# schematic.net
KiCad netlist of a schematic drawn in EasyEDA
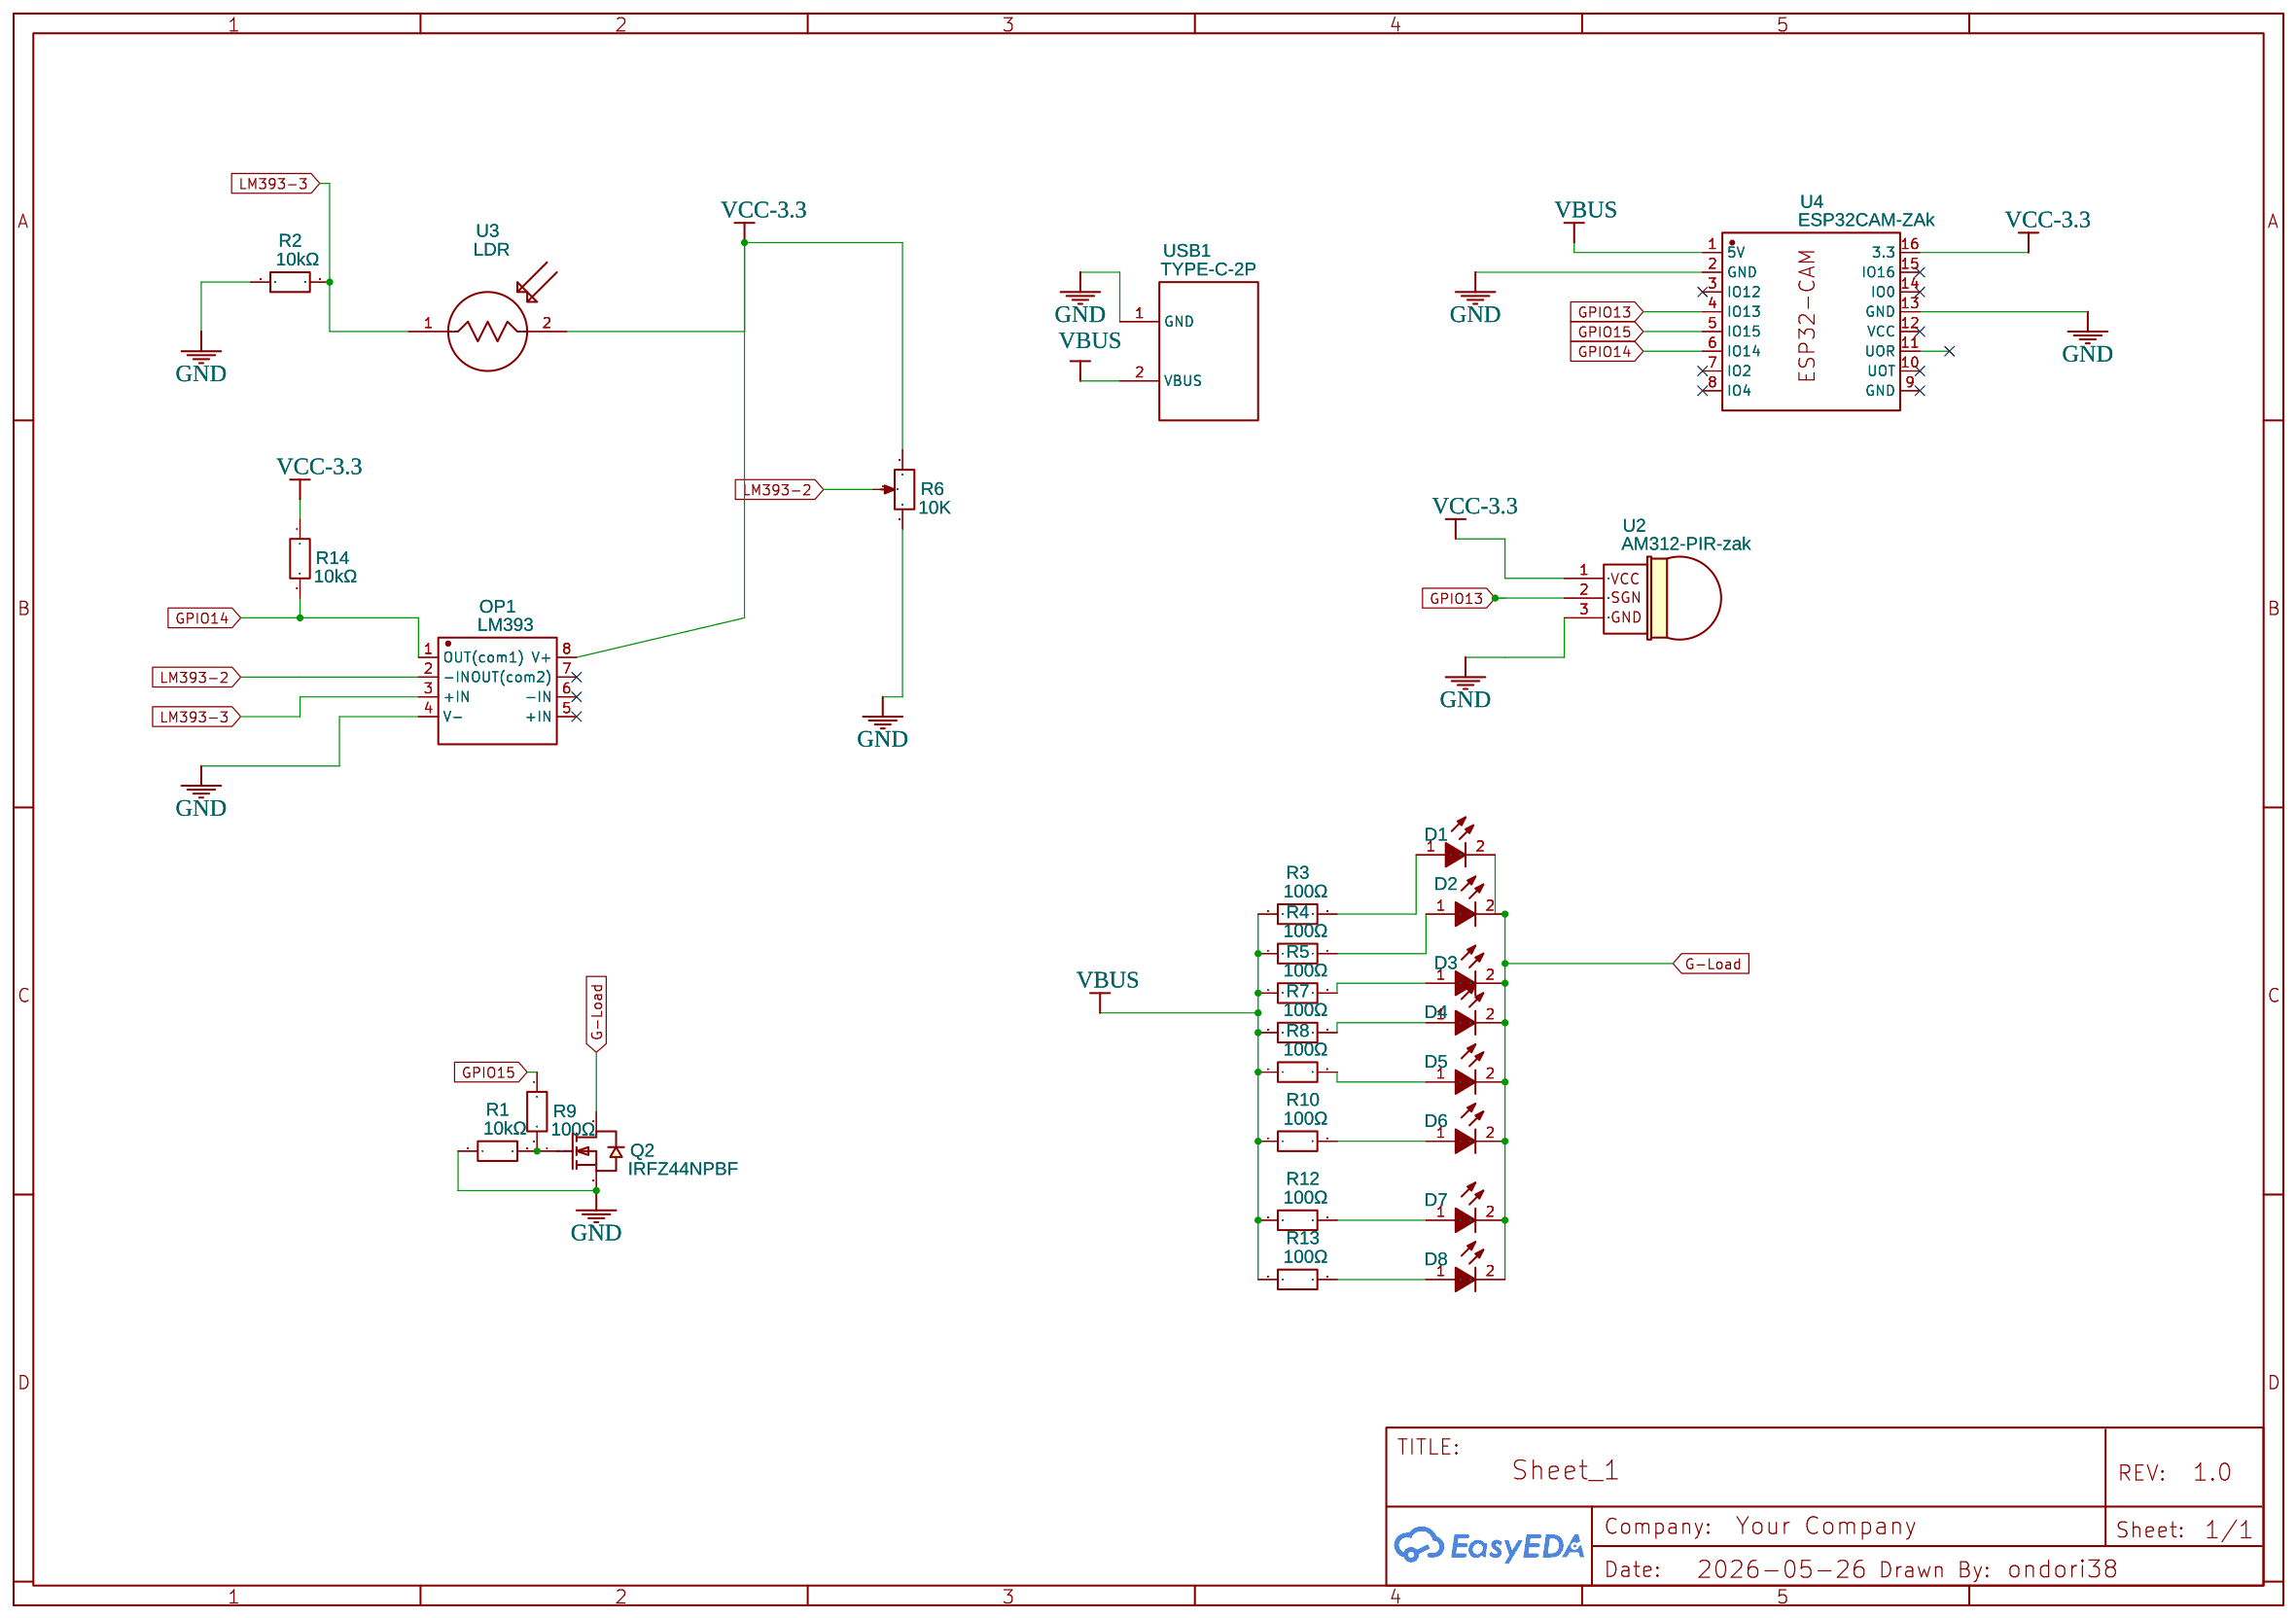
[diagram p0: schematic sheet]

(export (version "E")
  (design (tool "Eeschema 10.0.6"))
  (components
    (comp (ref "D1")
      (value "LED 2MM")
      (fields (field (name "Manufacturer Part") "5600") (field (name "Manufacturer") "VccLite"))
      (libsource (lib "") (part "LED 2MM"))
    )
    (comp (ref "D2")
      (value "LED 2MM")
      (fields (field (name "Manufacturer Part") "5600") (field (name "Manufacturer") "VccLite"))
      (libsource (lib "") (part "LED 2MM"))
    )
    (comp (ref "D3")
      (value "LED 2MM")
      (fields (field (name "Manufacturer Part") "5600") (field (name "Manufacturer") "VccLite"))
      (libsource (lib "") (part "LED 2MM"))
    )
    (comp (ref "D4")
      (value "LED 2MM")
      (fields (field (name "Manufacturer Part") "5600") (field (name "Manufacturer") "VccLite"))
      (libsource (lib "") (part "LED 2MM"))
    )
    (comp (ref "D5")
      (value "LED 2MM")
      (fields (field (name "Manufacturer Part") "5600") (field (name "Manufacturer") "VccLite"))
      (libsource (lib "") (part "LED 2MM"))
    )
    (comp (ref "D6")
      (value "LED 2MM")
      (fields (field (name "Manufacturer Part") "5600") (field (name "Manufacturer") "VccLite"))
      (libsource (lib "") (part "LED 2MM"))
    )
    (comp (ref "D7")
      (value "LED 2MM")
      (fields (field (name "Manufacturer Part") "5600") (field (name "Manufacturer") "VccLite"))
      (libsource (lib "") (part "LED 2MM"))
    )
    (comp (ref "D8")
      (value "LED 2MM")
      (fields (field (name "Manufacturer Part") "5600") (field (name "Manufacturer") "VccLite"))
      (libsource (lib "") (part "LED 2MM"))
    )
    (comp (ref "OP1") (value "LM393") (libsource (lib "") (part "LM393")))
    (comp (ref "Q2")
      (value "IRFZ44NPBF")
      (fields (field (name "Manufacturer") "Infineon(英飞凌)"))
      (libsource (lib "") (part "IRFZ44NPBF"))
    )
    (comp (ref "R1")
      (value "10kΩ")
      (fields (field (name "Manufacturer Part") "SCR1206F68K") (field (name "Manufacturer") "VO(翔胜)"))
      (libsource (lib "") (part "SCR1206F68K"))
    )
    (comp (ref "R2")
      (value "10kΩ")
      (fields (field (name "Manufacturer Part") "SCR1206F68K") (field (name "Manufacturer") "VO(翔胜)"))
      (libsource (lib "") (part "SCR1206F68K"))
    )
    (comp (ref "R3")
      (value "100Ω")
      (fields (field (name "Manufacturer Part") "SCR1206F68K") (field (name "Manufacturer") "VO(翔胜)"))
      (libsource (lib "") (part "SCR1206F68K"))
    )
    (comp (ref "R4")
      (value "100Ω")
      (fields (field (name "Manufacturer Part") "SCR1206F68K") (field (name "Manufacturer") "VO(翔胜)"))
      (libsource (lib "") (part "SCR1206F68K"))
    )
    (comp (ref "R5")
      (value "100Ω")
      (fields (field (name "Manufacturer Part") "SCR1206F68K") (field (name "Manufacturer") "VO(翔胜)"))
      (libsource (lib "") (part "SCR1206F68K"))
    )
    (comp (ref "R6")
      (value "10K")
      (fields
        (field (name "Manufacturer Part") "3296W-1-103")
        (field (name "Manufacturer") "Chengdu Guosheng Tech")
      )
      (libsource (lib "") (part "3296W-1-103_C330432"))
    )
    (comp (ref "R7")
      (value "100Ω")
      (fields (field (name "Manufacturer Part") "SCR1206F68K") (field (name "Manufacturer") "VO(翔胜)"))
      (libsource (lib "") (part "SCR1206F68K"))
    )
    (comp (ref "R8")
      (value "100Ω")
      (fields (field (name "Manufacturer Part") "SCR1206F68K") (field (name "Manufacturer") "VO(翔胜)"))
      (libsource (lib "") (part "SCR1206F68K"))
    )
    (comp (ref "R9")
      (value "100Ω")
      (fields (field (name "Manufacturer Part") "SCR1206F68K") (field (name "Manufacturer") "VO(翔胜)"))
      (libsource (lib "") (part "SCR1206F68K_1"))
    )
    (comp (ref "R10")
      (value "100Ω")
      (fields (field (name "Manufacturer Part") "SCR1206F68K") (field (name "Manufacturer") "VO(翔胜)"))
      (libsource (lib "") (part "SCR1206F68K"))
    )
    (comp (ref "R12")
      (value "100Ω")
      (fields (field (name "Manufacturer Part") "SCR1206F68K") (field (name "Manufacturer") "VO(翔胜)"))
      (libsource (lib "") (part "SCR1206F68K"))
    )
    (comp (ref "R13")
      (value "100Ω")
      (fields (field (name "Manufacturer Part") "SCR1206F68K") (field (name "Manufacturer") "VO(翔胜)"))
      (libsource (lib "") (part "SCR1206F68K"))
    )
    (comp (ref "R14")
      (value "10kΩ")
      (fields (field (name "Manufacturer Part") "SCR1206F68K") (field (name "Manufacturer") "VO(翔胜)"))
      (libsource (lib "") (part "SCR1206F68K_1"))
    )
    (comp (ref "U2") (value "AM312-PIR-zak") (libsource (lib "") (part "AM312-PIR-zak")))
    (comp (ref "U3") (value "LDR") (libsource (lib "") (part "LDR")))
    (comp (ref "U4") (value "ESP32CAM-ZAk") (libsource (lib "") (part "ESP32_CAM")))
    (comp (ref "USB1") (value "TYPE-C-2P") (libsource (lib "") (part "TYPE-C-2P")))
  )
  (nets
    (net (code "1") (name "G-Load") (class "Default")
      (node (ref "D1") (pin "2") (pinfunction "K_2") (pintype "input"))
      (node (ref "D2") (pin "2") (pinfunction "K_2") (pintype "input"))
      (node (ref "D3") (pin "2") (pinfunction "K_2") (pintype "input"))
      (node (ref "D4") (pin "2") (pinfunction "K_2") (pintype "input"))
      (node (ref "D5") (pin "2") (pinfunction "K_2") (pintype "input"))
      (node (ref "D6") (pin "2") (pinfunction "K_2") (pintype "input"))
      (node (ref "D7") (pin "2") (pinfunction "K_2") (pintype "input"))
      (node (ref "D8") (pin "2") (pinfunction "K_2") (pintype "input"))
      (node (ref "Q2") (pin "2") (pinfunction "D_2") (pintype "unspecified"))
    )
    (net (code "2") (name "GND") (class "Default")
      (node (ref "OP1") (pin "4") (pinfunction "V-_4") (pintype "unspecified"))
      (node (ref "Q2") (pin "3") (pinfunction "S_3") (pintype "unspecified"))
      (node (ref "R1") (pin "1") (pinfunction "1_1") (pintype "unspecified"))
      (node (ref "R2") (pin "1") (pinfunction "1_1") (pintype "unspecified"))
      (node (ref "R6") (pin "3") (pinfunction "3_3") (pintype "unspecified"))
      (node (ref "U2") (pin "3") (pinfunction "3_3") (pintype "unspecified"))
      (node (ref "U4") (pin "13") (pinfunction "GND_13") (pintype "unspecified"))
      (node (ref "U4") (pin "2") (pinfunction "GND_2") (pintype "unspecified"))
      (node (ref "USB1") (pin "1") (pinfunction "GND_1") (pintype "unspecified"))
    )
    (net (code "3") (name "GPIO13") (class "Default")
      (node (ref "U2") (pin "2") (pinfunction "2_2") (pintype "unspecified"))
      (node (ref "U4") (pin "4") (pinfunction "IO13_4") (pintype "unspecified"))
    )
    (net (code "4") (name "GPIO14") (class "Default")
      (node (ref "OP1") (pin "1") (pinfunction "OUT(com1)_1") (pintype "unspecified"))
      (node (ref "R14") (pin "2") (pinfunction "2_2") (pintype "unspecified"))
      (node (ref "U4") (pin "6") (pinfunction "IO14_6") (pintype "unspecified"))
    )
    (net (code "5") (name "GPIO15") (class "Default")
      (node (ref "R9") (pin "1") (pinfunction "1_1") (pintype "unspecified"))
      (node (ref "U4") (pin "5") (pinfunction "IO15_5") (pintype "unspecified"))
    )
    (net (code "6") (name "LM393-2") (class "Default")
      (node (ref "OP1") (pin "2") (pinfunction "-IN_2") (pintype "unspecified"))
      (node (ref "R6") (pin "2") (pinfunction "2_2") (pintype "unspecified"))
    )
    (net (code "7") (name "LM393-3") (class "Default")
      (node (ref "OP1") (pin "3") (pinfunction "+IN_3") (pintype "unspecified"))
      (node (ref "R2") (pin "2") (pinfunction "2_2") (pintype "unspecified"))
      (node (ref "U3") (pin "1") (pinfunction "1_1") (pintype "unspecified"))
    )
    (net (code "8") (name "Net-(D1-A)") (class "Default")
      (node (ref "D1") (pin "1") (pinfunction "A_1") (pintype "input"))
      (node (ref "R3") (pin "2") (pinfunction "2_2") (pintype "unspecified"))
    )
    (net (code "9") (name "Net-(D2-A)") (class "Default")
      (node (ref "D2") (pin "1") (pinfunction "A_1") (pintype "input"))
      (node (ref "R4") (pin "2") (pinfunction "2_2") (pintype "unspecified"))
    )
    (net (code "10") (name "Net-(D3-A)") (class "Default")
      (node (ref "D3") (pin "1") (pinfunction "A_1") (pintype "input"))
      (node (ref "R5") (pin "2") (pinfunction "2_2") (pintype "unspecified"))
    )
    (net (code "11") (name "Net-(D4-A)") (class "Default")
      (node (ref "D4") (pin "1") (pinfunction "A_1") (pintype "input"))
      (node (ref "R7") (pin "2") (pinfunction "2_2") (pintype "unspecified"))
    )
    (net (code "12") (name "Net-(D5-A)") (class "Default")
      (node (ref "D5") (pin "1") (pinfunction "A_1") (pintype "input"))
      (node (ref "R8") (pin "2") (pinfunction "2_2") (pintype "unspecified"))
    )
    (net (code "13") (name "Net-(D6-A)") (class "Default")
      (node (ref "D6") (pin "1") (pinfunction "A_1") (pintype "input"))
      (node (ref "R10") (pin "2") (pinfunction "2_2") (pintype "unspecified"))
    )
    (net (code "14") (name "Net-(D7-A)") (class "Default")
      (node (ref "D7") (pin "1") (pinfunction "A_1") (pintype "input"))
      (node (ref "R12") (pin "2") (pinfunction "2_2") (pintype "unspecified"))
    )
    (net (code "15") (name "Net-(D8-A)") (class "Default")
      (node (ref "D8") (pin "1") (pinfunction "A_1") (pintype "input"))
      (node (ref "R13") (pin "2") (pinfunction "2_2") (pintype "unspecified"))
    )
    (net (code "16") (name "Net-(Q2-G)") (class "Default")
      (node (ref "Q2") (pin "1") (pinfunction "G_1") (pintype "unspecified"))
      (node (ref "R1") (pin "2") (pinfunction "2_2") (pintype "unspecified"))
      (node (ref "R9") (pin "2") (pinfunction "2_2") (pintype "unspecified"))
    )
    (net (code "17") (name "VBUS") (class "Default")
      (node (ref "R10") (pin "1") (pinfunction "1_1") (pintype "unspecified"))
      (node (ref "R12") (pin "1") (pinfunction "1_1") (pintype "unspecified"))
      (node (ref "R13") (pin "1") (pinfunction "1_1") (pintype "unspecified"))
      (node (ref "R3") (pin "1") (pinfunction "1_1") (pintype "unspecified"))
      (node (ref "R4") (pin "1") (pinfunction "1_1") (pintype "unspecified"))
      (node (ref "R5") (pin "1") (pinfunction "1_1") (pintype "unspecified"))
      (node (ref "R7") (pin "1") (pinfunction "1_1") (pintype "unspecified"))
      (node (ref "R8") (pin "1") (pinfunction "1_1") (pintype "unspecified"))
      (node (ref "U4") (pin "1") (pinfunction "5V_1") (pintype "unspecified"))
      (node (ref "USB1") (pin "2") (pinfunction "VBUS_2") (pintype "unspecified"))
    )
    (net (code "18") (name "VCC-3.3") (class "Default")
      (node (ref "OP1") (pin "8") (pinfunction "V+_8") (pintype "unspecified"))
      (node (ref "R14") (pin "1") (pinfunction "1_1") (pintype "unspecified"))
      (node (ref "R6") (pin "1") (pinfunction "1_1") (pintype "unspecified"))
      (node (ref "U2") (pin "1") (pinfunction "1_1") (pintype "unspecified"))
      (node (ref "U3") (pin "2") (pinfunction "2_2") (pintype "unspecified"))
      (node (ref "U4") (pin "16") (pinfunction "3.3_16") (pintype "unspecified"))
    )
    (net (code "19") (name "unconnected-(OP1-+IN-Pad5)") (class "Default")
      (node (ref "OP1") (pin "5") (pinfunction "+IN_5") (pintype "unspecified+no_connect"))
    )
    (net (code "20") (name "unconnected-(OP1--IN-Pad6)") (class "Default")
      (node (ref "OP1") (pin "6") (pinfunction "-IN_6") (pintype "unspecified+no_connect"))
    )
    (net (code "21") (name "unconnected-(OP1-OUT(com2)-Pad7)") (class "Default")
      (node (ref "OP1") (pin "7") (pinfunction "OUT(com2)_7") (pintype "unspecified+no_connect"))
    )
    (net (code "22") (name "unconnected-(U4-GND-Pad9)") (class "Default")
      (node (ref "U4") (pin "9") (pinfunction "GND_9") (pintype "unspecified+no_connect"))
    )
    (net (code "23") (name "unconnected-(U4-IO0-Pad14)") (class "Default")
      (node (ref "U4") (pin "14") (pinfunction "IO0_14") (pintype "unspecified+no_connect"))
    )
    (net (code "24") (name "unconnected-(U4-IO2-Pad7)") (class "Default")
      (node (ref "U4") (pin "7") (pinfunction "IO2_7") (pintype "unspecified+no_connect"))
    )
    (net (code "25") (name "unconnected-(U4-IO4-Pad8)") (class "Default")
      (node (ref "U4") (pin "8") (pinfunction "IO4_8") (pintype "unspecified+no_connect"))
    )
    (net (code "26") (name "unconnected-(U4-IO12-Pad3)") (class "Default")
      (node (ref "U4") (pin "3") (pinfunction "IO12_3") (pintype "unspecified+no_connect"))
    )
    (net (code "27") (name "unconnected-(U4-IO16-Pad15)") (class "Default")
      (node (ref "U4") (pin "15") (pinfunction "IO16_15") (pintype "unspecified+no_connect"))
    )
    (net (code "28") (name "unconnected-(U4-UOR-Pad11)") (class "Default")
      (node (ref "U4") (pin "11") (pinfunction "UOR_11") (pintype "unspecified+no_connect"))
    )
    (net (code "29") (name "unconnected-(U4-UOT-Pad10)") (class "Default")
      (node (ref "U4") (pin "10") (pinfunction "UOT_10") (pintype "unspecified+no_connect"))
    )
    (net (code "30") (name "unconnected-(U4-VCC-Pad12)") (class "Default")
      (node (ref "U4") (pin "12") (pinfunction "VCC_12") (pintype "unspecified+no_connect"))
    )
  )
)
